# ProPrj__-END_2025-01-18.net
KiCad netlist of a schematic drawn in EasyEDA Pro
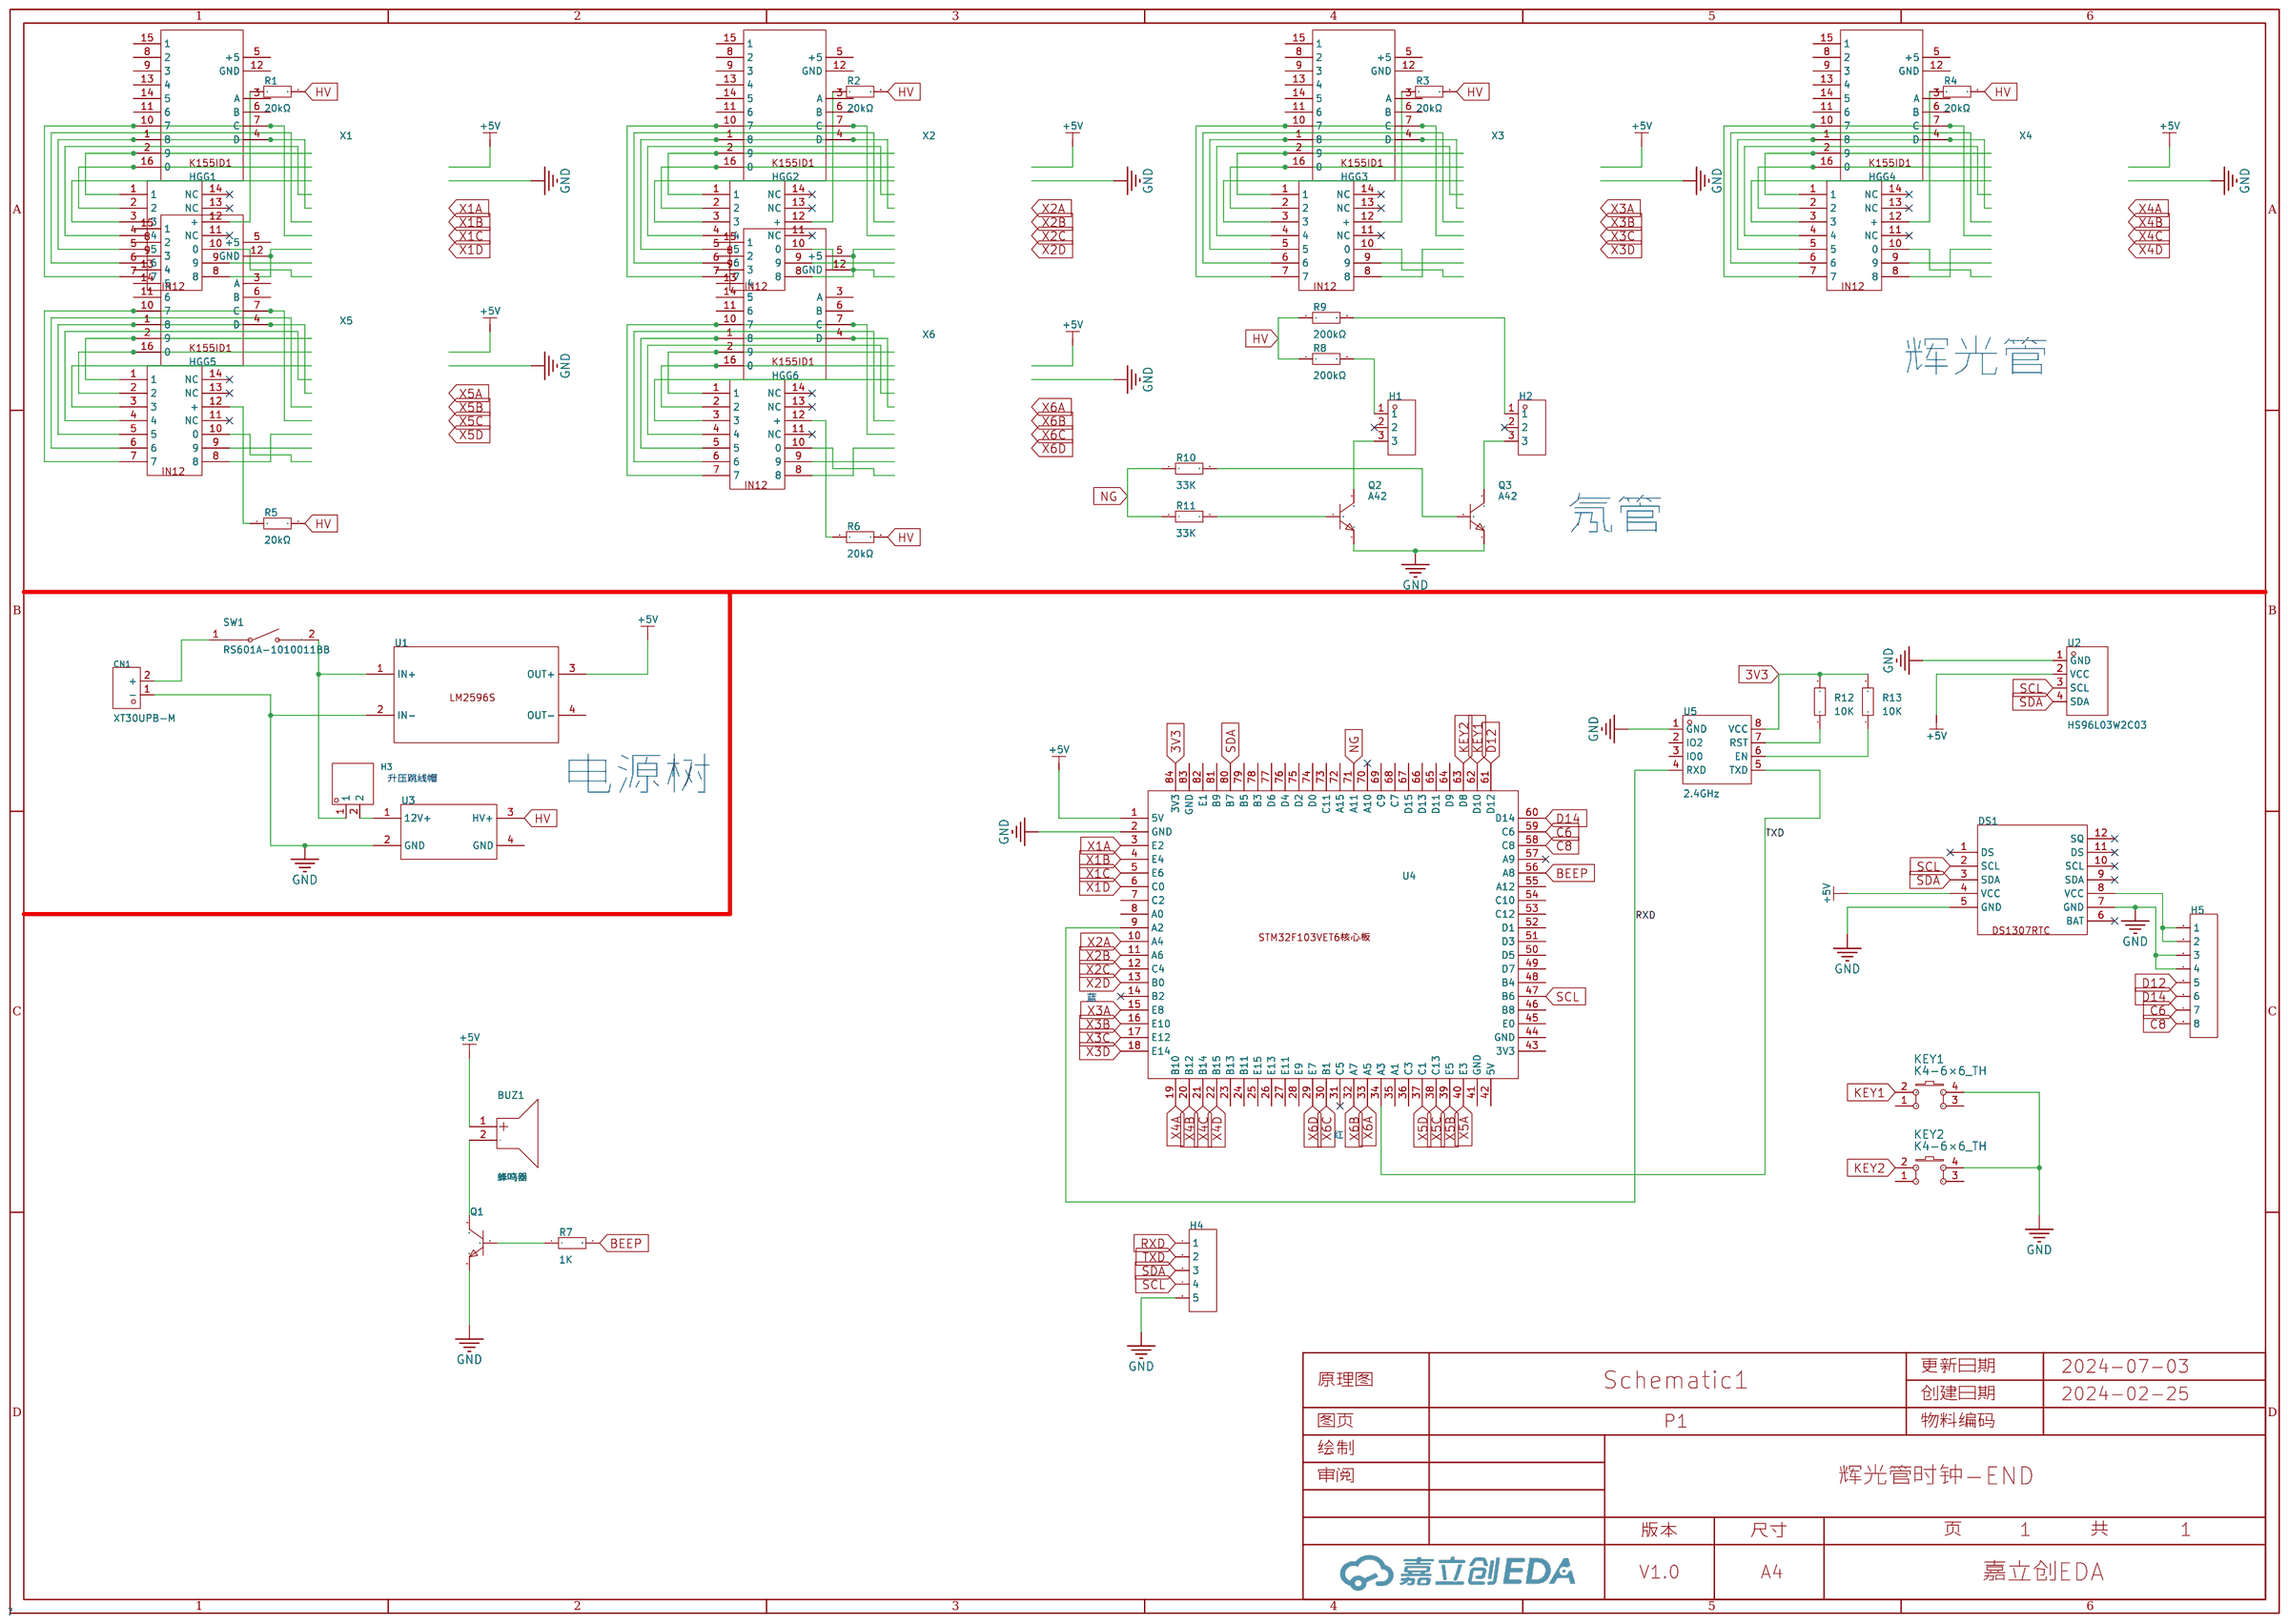
[diagram p0: schematic sheet]

(export (version "E")
  (design (tool "Eeschema 10.0.6"))
  (components
    (comp (ref "BUZ1")
      (value "蜂鸣器")
      (footprint "easyedapro:BUZ-TH_BD9.0-P5.00-D0.6-FD")
      (libsource (lib "easyedapro") (part "蜂鸣器"))
    )
    (comp (ref "CN1")
      (value "XT30UPB-M")
      (footprint "easyedapro:CONN-TH_XT30UPB-M")
      (description "类别:-;类型1:-;")
      (fields (field (name "Manufacturer") "AMASS(艾迈斯)"))
      (libsource (lib "easyedapro") (part "XT30UPB-M"))
    )
    (comp (ref "DS1")
      (value "~")
      (footprint "easyedapro:Tiny RTC")
      (description "DS1307模块")
      (libsource (lib "easyedapro") (part "DS1307模块IIC"))
    )
    (comp (ref "H1")
      (value "~")
      (footprint "easyedapro:HDR-TH_3P-P2.54-V-F")
      (libsource (lib "easyedapro") (part "PM254V-11-03-H85"))
    )
    (comp (ref "H2")
      (value "~")
      (footprint "easyedapro:HDR-TH_3P-P2.54-V-F")
      (libsource (lib "easyedapro") (part "PM254V-11-03-H85"))
    )
    (comp (ref "H3")
      (value "~")
      (footprint "easyedapro:HDR-TH_2P-P2.54-V-M-1")
      (libsource (lib "easyedapro") (part "210S-1*2P L=11.6MMGold-plated black"))
    )
    (comp (ref "H4")
      (value "~")
      (footprint "easyedapro:HDR-TH_5P-P2.54-V-F")
      (libsource (lib "easyedapro") (part "Header-Female-2.54_1x5"))
    )
    (comp (ref "H5")
      (value "~")
      (footprint "easyedapro:HDR-TH_8P-P2.54-V-F-1")
      (libsource (lib "easyedapro") (part "Header-Female-2.54_1x8"))
    )
    (comp (ref "HGG1")
      (value "~")
      (footprint "easyedapro:IN12-6")
      (libsource (lib "easyedapro") (part "辉光管IN12"))
    )
    (comp (ref "HGG2")
      (value "~")
      (footprint "easyedapro:IN12-6")
      (libsource (lib "easyedapro") (part "辉光管IN12"))
    )
    (comp (ref "HGG3")
      (value "~")
      (footprint "easyedapro:IN12-6")
      (libsource (lib "easyedapro") (part "辉光管IN12"))
    )
    (comp (ref "HGG4")
      (value "~")
      (footprint "easyedapro:IN12-6")
      (libsource (lib "easyedapro") (part "辉光管IN12"))
    )
    (comp (ref "HGG5")
      (value "~")
      (footprint "easyedapro:IN12-6")
      (libsource (lib "easyedapro") (part "辉光管IN12"))
    )
    (comp (ref "HGG6")
      (value "~")
      (footprint "easyedapro:IN12-6")
      (libsource (lib "easyedapro") (part "辉光管IN12"))
    )
    (comp (ref "KEY1")
      (value "K4-6×6_TH")
      (footprint "easyedapro:KEY-TH_4P-L6.0-W6.0-P4.50-LS6.5")
      (fields (field (name "Manufacturer Part") "K2-1102DP-E4SW-04") (field (name "Manufacturer") "韩国韩荣"))
      (libsource (lib "easyedapro") (part "K4-6×6_TH"))
    )
    (comp (ref "KEY2")
      (value "K4-6×6_TH")
      (footprint "easyedapro:KEY-TH_4P-L6.0-W6.0-P4.50-LS6.5")
      (fields (field (name "Manufacturer Part") "K2-1102DP-E4SW-04") (field (name "Manufacturer") "韩国韩荣"))
      (libsource (lib "easyedapro") (part "K4-6×6_TH"))
    )
    (comp (ref "Q1")
      (value "~")
      (footprint "easyedapro:S8050_SOT-23")
      (libsource (lib "easyedapro") (part "NPN"))
    )
    (comp (ref "Q2")
      (value "A42")
      (footprint "easyedapro:TO-92-3_L5.1-W4.1-P1.27-L")
      (description "晶体管类型:NPN;集电极电流(Ic):200mA;集射极击穿电压(Vceo):305V;功率(Pd):625mW;直流电流增益(hFE@Ic,Vce):100@10mA,10V;")
      (fields (field (name "Manufacturer") "CJ(江苏长电/长晶)"))
      (libsource (lib "easyedapro") (part "A42"))
    )
    (comp (ref "Q3")
      (value "A42")
      (footprint "easyedapro:TO-92-3_L5.1-W4.1-P1.27-L")
      (description "晶体管类型:NPN;集电极电流(Ic):200mA;集射极击穿电压(Vceo):305V;功率(Pd):625mW;直流电流增益(hFE@Ic,Vce):100@10mA,10V;")
      (fields (field (name "Manufacturer") "CJ(江苏长电/长晶)"))
      (libsource (lib "easyedapro") (part "A42"))
    )
    (comp (ref "R1")
      (value "20kΩ")
      (footprint "easyedapro:RES-TH_BD2.2-L6.5-P10.50-D0.6")
      (description "电阻类型:金属膜电阻;阻值:20kΩ;精度:±1%;功率:250mW;温度系数:±50ppm/°C;")
      (fields
        (field (name "Manufacturer Part") "MFR0W4F2002A50")
        (field (name "Manufacturer") "UNI-ROYAL(厚声)")
      )
      (libsource (lib "easyedapro") (part "MFR0W4F2002A50"))
    )
    (comp (ref "R2")
      (value "20kΩ")
      (footprint "easyedapro:RES-TH_BD2.2-L6.5-P10.50-D0.6")
      (description "电阻类型:金属膜电阻;阻值:20kΩ;精度:±1%;功率:250mW;温度系数:±50ppm/°C;")
      (fields
        (field (name "Manufacturer Part") "MFR0W4F2002A50")
        (field (name "Manufacturer") "UNI-ROYAL(厚声)")
      )
      (libsource (lib "easyedapro") (part "MFR0W4F2002A50"))
    )
    (comp (ref "R3")
      (value "20kΩ")
      (footprint "easyedapro:RES-TH_BD2.2-L6.5-P10.50-D0.6")
      (description "电阻类型:金属膜电阻;阻值:20kΩ;精度:±1%;功率:250mW;温度系数:±50ppm/°C;")
      (fields
        (field (name "Manufacturer Part") "MFR0W4F2002A50")
        (field (name "Manufacturer") "UNI-ROYAL(厚声)")
      )
      (libsource (lib "easyedapro") (part "MFR0W4F2002A50"))
    )
    (comp (ref "R4")
      (value "20kΩ")
      (footprint "easyedapro:RES-TH_BD2.2-L6.5-P10.50-D0.6")
      (description "电阻类型:金属膜电阻;阻值:20kΩ;精度:±1%;功率:250mW;温度系数:±50ppm/°C;")
      (fields
        (field (name "Manufacturer Part") "MFR0W4F2002A50")
        (field (name "Manufacturer") "UNI-ROYAL(厚声)")
      )
      (libsource (lib "easyedapro") (part "MFR0W4F2002A50"))
    )
    (comp (ref "R5")
      (value "20kΩ")
      (footprint "easyedapro:RES-TH_BD2.2-L6.5-P10.50-D0.6")
      (description "电阻类型:金属膜电阻;阻值:20kΩ;精度:±1%;功率:250mW;温度系数:±50ppm/°C;")
      (fields
        (field (name "Manufacturer Part") "MFR0W4F2002A50")
        (field (name "Manufacturer") "UNI-ROYAL(厚声)")
      )
      (libsource (lib "easyedapro") (part "MFR0W4F2002A50"))
    )
    (comp (ref "R6")
      (value "20kΩ")
      (footprint "easyedapro:RES-TH_BD2.2-L6.5-P10.50-D0.6")
      (description "电阻类型:金属膜电阻;阻值:20kΩ;精度:±1%;功率:250mW;温度系数:±50ppm/°C;")
      (fields
        (field (name "Manufacturer Part") "MFR0W4F2002A50")
        (field (name "Manufacturer") "UNI-ROYAL(厚声)")
      )
      (libsource (lib "easyedapro") (part "MFR0W4F2002A50"))
    )
    (comp (ref "R7") (value "1K") (footprint "easyedapro:R0805") (libsource (lib "easyedapro") (part "电阻")))
    (comp (ref "R8")
      (value "200kΩ")
      (footprint "easyedapro:R0805")
      (libsource (lib "easyedapro") (part "电阻"))
    )
    (comp (ref "R9")
      (value "200kΩ")
      (footprint "easyedapro:R0805")
      (libsource (lib "easyedapro") (part "电阻"))
    )
    (comp (ref "R10") (value "33K") (footprint "easyedapro:R0805") (libsource (lib "easyedapro") (part "电阻")))
    (comp (ref "R11") (value "33K") (footprint "easyedapro:R0805") (libsource (lib "easyedapro") (part "电阻")))
    (comp (ref "R12") (value "10K") (footprint "easyedapro:R0805") (libsource (lib "easyedapro") (part "电阻")))
    (comp (ref "R13") (value "10K") (footprint "easyedapro:R0805") (libsource (lib "easyedapro") (part "电阻")))
    (comp (ref "SW1")
      (value "RS601A-1010011BB")
      (footprint "easyedapro:SW-TH_RS601A-1010011BB")
      (fields (field (name "Manufacturer") "LECI(乐磁)"))
      (libsource (lib "easyedapro") (part "RS601A-1010011BB"))
    )
    (comp (ref "U1")
      (value "~")
      (footprint "easyedapro:LM2596S降压模块")
      (libsource (lib "easyedapro") (part "LM2569S降压模块"))
    )
    (comp (ref "U2")
      (value "HS96L03W2C03")
      (footprint "easyedapro:OLED-TH_L27.8-W27.2-P2.54_C9900033791")
      (description "主控芯片:SSD1315;接口类型:I2C;尺寸(inch):0.96;像素分辨率:128x64;")
      (fields (field (name "Manufacturer") "HS(汉昇)"))
      (libsource (lib "easyedapro") (part "HS96L03W2C03"))
    )
    (comp (ref "U3")
      (value "~")
      (footprint "easyedapro:升压模块2")
      (description "给辉光管升压的模块")
      (libsource (lib "easyedapro") (part "辉光管升压模块"))
    )
    (comp (ref "U4")
      (value "~")
      (footprint "easyedapro:魔女STM32F103VET6核心板")
      (libsource (lib "easyedapro") (part "魔女STM32F103VET6核心板"))
    )
    (comp (ref "U5")
      (value "2.4GHz")
      (footprint "easyedapro:WIFIM-TH_8P-L24.7-W14.4-P2.54")
      (description "核心处理器:ESP8266芯片;频率:2.4GHz;天线形式:板载PCB天线;发射功率:16dBm;接收灵敏度:-90dBm;")
      (fields (field (name "Manufacturer Part") "ESP-01S") (field (name "Manufacturer") "Ai-Thinker(安信可)"))
      (libsource (lib "easyedapro") (part "ESP-01S_C503582"))
    )
    (comp (ref "X1")
      (value "~")
      (footprint "easyedapro:K155ID1")
      (libsource (lib "easyedapro") (part "K155ID1"))
    )
    (comp (ref "X2")
      (value "~")
      (footprint "easyedapro:K155ID1")
      (libsource (lib "easyedapro") (part "K155ID1"))
    )
    (comp (ref "X3")
      (value "~")
      (footprint "easyedapro:K155ID1")
      (libsource (lib "easyedapro") (part "K155ID1"))
    )
    (comp (ref "X4")
      (value "~")
      (footprint "easyedapro:K155ID1")
      (libsource (lib "easyedapro") (part "K155ID1"))
    )
    (comp (ref "X5")
      (value "~")
      (footprint "easyedapro:K155ID1")
      (libsource (lib "easyedapro") (part "K155ID1"))
    )
    (comp (ref "X6")
      (value "~")
      (footprint "easyedapro:K155ID1")
      (libsource (lib "easyedapro") (part "K155ID1"))
    )
  )
  (nets
    (net (code "1") (name "+5V") (class "Default")
      (node (ref "BUZ1") (pin "1") (pinfunction "+_1") (pintype "unspecified"))
      (node (ref "DS1") (pin "4") (pinfunction "VCC_4") (pintype "input"))
      (node (ref "U1") (pin "3") (pinfunction "OUT+_3") (pintype "input"))
      (node (ref "U2") (pin "2") (pinfunction "VCC_2") (pintype "unspecified"))
      (node (ref "U4") (pin "1") (pinfunction "5V_1") (pintype "input"))
    )
    (net (code "2") (name "3V3") (class "Default")
      (node (ref "R12") (pin "2") (pinfunction "2_2") (pintype "input"))
      (node (ref "R13") (pin "2") (pinfunction "2_2") (pintype "input"))
      (node (ref "U4") (pin "84") (pinfunction "3V3_84") (pintype "input"))
      (node (ref "U5") (pin "8") (pinfunction "VCC_8") (pintype "input"))
    )
    (net (code "3") (name "BEEP") (class "Default")
      (node (ref "R7") (pin "2") (pinfunction "2_2") (pintype "input"))
      (node (ref "U4") (pin "56") (pinfunction "A8_56") (pintype "input"))
    )
    (net (code "4") (name "C6") (class "Default")
      (node (ref "H5") (pin "7") (pinfunction "7_7") (pintype "input"))
      (node (ref "U4") (pin "59") (pinfunction "C6_59") (pintype "input"))
    )
    (net (code "5") (name "C8") (class "Default")
      (node (ref "H5") (pin "8") (pinfunction "8_8") (pintype "input"))
      (node (ref "U4") (pin "58") (pinfunction "C8_58") (pintype "input"))
    )
    (net (code "6") (name "D12") (class "Default")
      (node (ref "H5") (pin "5") (pinfunction "5_5") (pintype "input"))
      (node (ref "U4") (pin "61") (pinfunction "D12_61") (pintype "input"))
    )
    (net (code "7") (name "D14") (class "Default")
      (node (ref "H5") (pin "6") (pinfunction "6_6") (pintype "input"))
      (node (ref "U4") (pin "60") (pinfunction "D14_60") (pintype "input"))
    )
    (net (code "8") (name "GND") (class "Default")
      (node (ref "CN1") (pin "1") (pinfunction "-_1") (pintype "input"))
      (node (ref "DS1") (pin "5") (pinfunction "GND_5") (pintype "input"))
      (node (ref "DS1") (pin "7") (pinfunction "GND_7") (pintype "input"))
      (node (ref "H4") (pin "5") (pinfunction "5_5") (pintype "input"))
      (node (ref "H5") (pin "3") (pinfunction "3_3") (pintype "input"))
      (node (ref "H5") (pin "4") (pinfunction "4_4") (pintype "input"))
      (node (ref "KEY1") (pin "4") (pinfunction "4_4") (pintype "input"))
      (node (ref "KEY2") (pin "4") (pinfunction "4_4") (pintype "input"))
      (node (ref "Q1") (pin "2") (pinfunction "2_2") (pintype "unspecified"))
      (node (ref "Q2") (pin "1") (pinfunction "E_1") (pintype "unspecified"))
      (node (ref "Q3") (pin "1") (pinfunction "E_1") (pintype "unspecified"))
      (node (ref "U1") (pin "2") (pinfunction "IN-_2") (pintype "input"))
      (node (ref "U2") (pin "1") (pinfunction "GND_1") (pintype "unspecified"))
      (node (ref "U3") (pin "2") (pinfunction "GND_2") (pintype "input"))
      (node (ref "U4") (pin "2") (pinfunction "GND_2") (pintype "input"))
      (node (ref "U5") (pin "1") (pinfunction "GND_1") (pintype "input"))
    )
    (net (code "9") (name "HV") (class "Default")
      (node (ref "R1") (pin "2") (pinfunction "2_2") (pintype "input"))
      (node (ref "R2") (pin "2") (pinfunction "2_2") (pintype "input"))
      (node (ref "R3") (pin "2") (pinfunction "2_2") (pintype "input"))
      (node (ref "R4") (pin "2") (pinfunction "2_2") (pintype "input"))
      (node (ref "R5") (pin "2") (pinfunction "2_2") (pintype "input"))
      (node (ref "R6") (pin "2") (pinfunction "2_2") (pintype "input"))
      (node (ref "R8") (pin "1") (pinfunction "1_1") (pintype "input"))
      (node (ref "R9") (pin "1") (pinfunction "1_1") (pintype "input"))
      (node (ref "U3") (pin "3") (pinfunction "HV+_3") (pintype "input"))
    )
    (net (code "10") (name "KEY1") (class "Default")
      (node (ref "KEY1") (pin "2") (pinfunction "2_2") (pintype "input"))
      (node (ref "U4") (pin "62") (pinfunction "D10_62") (pintype "input"))
    )
    (net (code "11") (name "KEY2") (class "Default")
      (node (ref "KEY2") (pin "2") (pinfunction "2_2") (pintype "input"))
      (node (ref "U4") (pin "63") (pinfunction "D8_63") (pintype "input"))
    )
    (net (code "12") (name "NG") (class "Default")
      (node (ref "R10") (pin "1") (pinfunction "1_1") (pintype "input"))
      (node (ref "R11") (pin "1") (pinfunction "1_1") (pintype "input"))
      (node (ref "U4") (pin "71") (pinfunction "A11_71") (pintype "input"))
    )
    (net (code "13") (name "Net-(BUZ1--)") (class "Default")
      (node (ref "BUZ1") (pin "2") (pinfunction "-_2") (pintype "unspecified"))
      (node (ref "Q1") (pin "3") (pinfunction "3_3") (pintype "unspecified"))
    )
    (net (code "14") (name "Net-(CN1-+)") (class "Default")
      (node (ref "CN1") (pin "2") (pinfunction "+_2") (pintype "input"))
      (node (ref "SW1") (pin "1") (pinfunction "1_1") (pintype "input"))
    )
    (net (code "15") (name "Net-(DS1-VCC-Pad8)") (class "Default")
      (node (ref "DS1") (pin "8") (pinfunction "VCC_8") (pintype "input"))
      (node (ref "H5") (pin "1") (pinfunction "1_1") (pintype "input"))
      (node (ref "H5") (pin "2") (pinfunction "2_2") (pintype "input"))
    )
    (net (code "16") (name "Net-(H1-Pad1)") (class "Default")
      (node (ref "H1") (pin "1") (pinfunction "1_1") (pintype "unspecified"))
      (node (ref "R8") (pin "2") (pinfunction "2_2") (pintype "input"))
    )
    (net (code "17") (name "Net-(H2-Pad1)") (class "Default")
      (node (ref "H2") (pin "1") (pinfunction "1_1") (pintype "unspecified"))
      (node (ref "R9") (pin "2") (pinfunction "2_2") (pintype "input"))
    )
    (net (code "18") (name "Net-(HGG1-+)") (class "Default")
      (node (ref "HGG1") (pin "12") (pinfunction "+_12") (pintype "input"))
      (node (ref "R1") (pin "1") (pinfunction "1_1") (pintype "input"))
    )
    (net (code "19") (name "Net-(HGG2-+)") (class "Default")
      (node (ref "HGG2") (pin "12") (pinfunction "+_12") (pintype "input"))
      (node (ref "R2") (pin "1") (pinfunction "1_1") (pintype "input"))
    )
    (net (code "20") (name "Net-(HGG2-0)") (class "Default")
      (node (ref "HGG2") (pin "10") (pinfunction "0_10") (pintype "input"))
      (node (ref "HGG2") (pin "8") (pinfunction "8_8") (pintype "input"))
      (node (ref "X6") (pin "12") (pinfunction "GND_12") (pintype "input"))
      (node (ref "X6") (pin "5") (pinfunction "+5_5") (pintype "input"))
    )
    (net (code "21") (name "Net-(HGG3-+)") (class "Default")
      (node (ref "HGG3") (pin "12") (pinfunction "+_12") (pintype "input"))
      (node (ref "R3") (pin "1") (pinfunction "1_1") (pintype "input"))
    )
    (net (code "22") (name "Net-(HGG4-+)") (class "Default")
      (node (ref "HGG4") (pin "12") (pinfunction "+_12") (pintype "input"))
      (node (ref "R4") (pin "1") (pinfunction "1_1") (pintype "input"))
    )
    (net (code "23") (name "Net-(HGG5-+)") (class "Default")
      (node (ref "HGG5") (pin "12") (pinfunction "+_12") (pintype "input"))
      (node (ref "R5") (pin "1") (pinfunction "1_1") (pintype "input"))
    )
    (net (code "24") (name "Net-(HGG6-+)") (class "Default")
      (node (ref "HGG6") (pin "12") (pinfunction "+_12") (pintype "input"))
      (node (ref "R6") (pin "1") (pinfunction "1_1") (pintype "input"))
    )
    (net (code "25") (name "Net-(Q1-Pad1)") (class "Default")
      (node (ref "Q1") (pin "1") (pinfunction "1_1") (pintype "unspecified"))
      (node (ref "R7") (pin "1") (pinfunction "1_1") (pintype "input"))
    )
    (net (code "26") (name "Net-(Q2-B)") (class "Default")
      (node (ref "Q2") (pin "2") (pinfunction "B_2") (pintype "unspecified"))
      (node (ref "R11") (pin "2") (pinfunction "2_2") (pintype "input"))
    )
    (net (code "27") (name "Net-(Q2-C)") (class "Default")
      (node (ref "H1") (pin "3") (pinfunction "3_3") (pintype "unspecified"))
      (node (ref "Q2") (pin "3") (pinfunction "C_3") (pintype "unspecified"))
    )
    (net (code "28") (name "Net-(Q3-B)") (class "Default")
      (node (ref "Q3") (pin "2") (pinfunction "B_2") (pintype "unspecified"))
      (node (ref "R10") (pin "2") (pinfunction "2_2") (pintype "input"))
    )
    (net (code "29") (name "Net-(Q3-C)") (class "Default")
      (node (ref "H2") (pin "3") (pinfunction "3_3") (pintype "unspecified"))
      (node (ref "Q3") (pin "3") (pinfunction "C_3") (pintype "unspecified"))
    )
    (net (code "30") (name "Net-(U1-IN+)") (class "Default")
      (node (ref "H3") (pin "1") (pinfunction "1_1") (pintype "input"))
      (node (ref "SW1") (pin "2") (pinfunction "2_2") (pintype "input"))
      (node (ref "U1") (pin "1") (pinfunction "IN+_1") (pintype "input"))
    )
    (net (code "31") (name "Net-(U3-12V+)") (class "Default")
      (node (ref "H3") (pin "2") (pinfunction "2_2") (pintype "input"))
      (node (ref "U3") (pin "1") (pinfunction "12V+_1") (pintype "input"))
    )
    (net (code "32") (name "Net-(U5-EN)") (class "Default")
      (node (ref "R13") (pin "1") (pinfunction "1_1") (pintype "input"))
      (node (ref "U5") (pin "6") (pinfunction "EN_6") (pintype "input"))
    )
    (net (code "33") (name "Net-(U5-RST)") (class "Default")
      (node (ref "R12") (pin "1") (pinfunction "1_1") (pintype "input"))
      (node (ref "U5") (pin "7") (pinfunction "RST_7") (pintype "input"))
    )
    (net (code "34") (name "Net-(X1-0)") (class "Default")
      (node (ref "HGG1") (pin "2") (pinfunction "2_2") (pintype "input"))
      (node (ref "X1") (pin "16") (pinfunction "0_16") (pintype "input"))
    )
    (net (code "35") (name "Net-(X1-7)") (class "Default")
      (node (ref "HGG1") (pin "7") (pinfunction "7_7") (pintype "input"))
      (node (ref "X1") (pin "10") (pinfunction "7_10") (pintype "input"))
      (node (ref "X1") (pin "7") (pinfunction "C_7") (pintype "input"))
    )
    (net (code "36") (name "Net-(X1-8)") (class "Default")
      (node (ref "HGG1") (pin "5") (pinfunction "5_5") (pintype "input"))
      (node (ref "X1") (pin "1") (pinfunction "8_1") (pintype "input"))
      (node (ref "X1") (pin "4") (pinfunction "D_4") (pintype "input"))
    )
    (net (code "37") (name "Net-(X1-9)") (class "Default")
      (node (ref "HGG1") (pin "1") (pinfunction "1_1") (pintype "input"))
      (node (ref "X1") (pin "2") (pinfunction "9_2") (pintype "input"))
    )
    (net (code "38") (name "Net-(X2-0)") (class "Default")
      (node (ref "HGG2") (pin "2") (pinfunction "2_2") (pintype "input"))
      (node (ref "X2") (pin "16") (pinfunction "0_16") (pintype "input"))
    )
    (net (code "39") (name "Net-(X2-7)") (class "Default")
      (node (ref "HGG2") (pin "7") (pinfunction "7_7") (pintype "input"))
      (node (ref "X2") (pin "10") (pinfunction "7_10") (pintype "input"))
      (node (ref "X2") (pin "7") (pinfunction "C_7") (pintype "input"))
    )
    (net (code "40") (name "Net-(X2-8)") (class "Default")
      (node (ref "HGG2") (pin "5") (pinfunction "5_5") (pintype "input"))
      (node (ref "X2") (pin "1") (pinfunction "8_1") (pintype "input"))
      (node (ref "X2") (pin "4") (pinfunction "D_4") (pintype "input"))
    )
    (net (code "41") (name "Net-(X2-9)") (class "Default")
      (node (ref "HGG2") (pin "1") (pinfunction "1_1") (pintype "input"))
      (node (ref "X2") (pin "2") (pinfunction "9_2") (pintype "input"))
    )
    (net (code "42") (name "Net-(X3-0)") (class "Default")
      (node (ref "HGG3") (pin "2") (pinfunction "2_2") (pintype "input"))
      (node (ref "X3") (pin "16") (pinfunction "0_16") (pintype "input"))
    )
    (net (code "43") (name "Net-(X3-7)") (class "Default")
      (node (ref "HGG3") (pin "7") (pinfunction "7_7") (pintype "input"))
      (node (ref "X3") (pin "10") (pinfunction "7_10") (pintype "input"))
      (node (ref "X3") (pin "7") (pinfunction "C_7") (pintype "input"))
    )
    (net (code "44") (name "Net-(X3-8)") (class "Default")
      (node (ref "HGG3") (pin "5") (pinfunction "5_5") (pintype "input"))
      (node (ref "X3") (pin "1") (pinfunction "8_1") (pintype "input"))
      (node (ref "X3") (pin "4") (pinfunction "D_4") (pintype "input"))
    )
    (net (code "45") (name "Net-(X3-9)") (class "Default")
      (node (ref "HGG3") (pin "1") (pinfunction "1_1") (pintype "input"))
      (node (ref "X3") (pin "2") (pinfunction "9_2") (pintype "input"))
    )
    (net (code "46") (name "Net-(X4-0)") (class "Default")
      (node (ref "HGG4") (pin "2") (pinfunction "2_2") (pintype "input"))
      (node (ref "X4") (pin "16") (pinfunction "0_16") (pintype "input"))
    )
    (net (code "47") (name "Net-(X4-7)") (class "Default")
      (node (ref "HGG4") (pin "7") (pinfunction "7_7") (pintype "input"))
      (node (ref "X4") (pin "10") (pinfunction "7_10") (pintype "input"))
      (node (ref "X4") (pin "7") (pinfunction "C_7") (pintype "input"))
    )
    (net (code "48") (name "Net-(X4-8)") (class "Default")
      (node (ref "HGG4") (pin "5") (pinfunction "5_5") (pintype "input"))
      (node (ref "X4") (pin "1") (pinfunction "8_1") (pintype "input"))
      (node (ref "X4") (pin "4") (pinfunction "D_4") (pintype "input"))
    )
    (net (code "49") (name "Net-(X4-9)") (class "Default")
      (node (ref "HGG4") (pin "1") (pinfunction "1_1") (pintype "input"))
      (node (ref "X4") (pin "2") (pinfunction "9_2") (pintype "input"))
    )
    (net (code "50") (name "Net-(X5-0)") (class "Default")
      (node (ref "HGG5") (pin "2") (pinfunction "2_2") (pintype "input"))
      (node (ref "X5") (pin "16") (pinfunction "0_16") (pintype "input"))
    )
    (net (code "51") (name "Net-(X5-7)") (class "Default")
      (node (ref "HGG5") (pin "7") (pinfunction "7_7") (pintype "input"))
      (node (ref "X5") (pin "10") (pinfunction "7_10") (pintype "input"))
      (node (ref "X5") (pin "7") (pinfunction "C_7") (pintype "input"))
    )
    (net (code "52") (name "Net-(X5-8)") (class "Default")
      (node (ref "HGG5") (pin "5") (pinfunction "5_5") (pintype "input"))
      (node (ref "X5") (pin "1") (pinfunction "8_1") (pintype "input"))
      (node (ref "X5") (pin "4") (pinfunction "D_4") (pintype "input"))
    )
    (net (code "53") (name "Net-(X5-9)") (class "Default")
      (node (ref "HGG5") (pin "1") (pinfunction "1_1") (pintype "input"))
      (node (ref "X5") (pin "2") (pinfunction "9_2") (pintype "input"))
    )
    (net (code "54") (name "Net-(X5-GND)") (class "Default")
      (node (ref "HGG1") (pin "8") (pinfunction "8_8") (pintype "input"))
      (node (ref "X5") (pin "12") (pinfunction "GND_12") (pintype "input"))
    )
    (net (code "55") (name "Net-(X6-0)") (class "Default")
      (node (ref "HGG6") (pin "2") (pinfunction "2_2") (pintype "input"))
      (node (ref "X6") (pin "16") (pinfunction "0_16") (pintype "input"))
    )
    (net (code "56") (name "Net-(X6-7)") (class "Default")
      (node (ref "HGG6") (pin "7") (pinfunction "7_7") (pintype "input"))
      (node (ref "X6") (pin "10") (pinfunction "7_10") (pintype "input"))
      (node (ref "X6") (pin "7") (pinfunction "C_7") (pintype "input"))
    )
    (net (code "57") (name "Net-(X6-8)") (class "Default")
      (node (ref "HGG6") (pin "5") (pinfunction "5_5") (pintype "input"))
      (node (ref "X6") (pin "1") (pinfunction "8_1") (pintype "input"))
      (node (ref "X6") (pin "4") (pinfunction "D_4") (pintype "input"))
    )
    (net (code "58") (name "Net-(X6-9)") (class "Default")
      (node (ref "HGG6") (pin "1") (pinfunction "1_1") (pintype "input"))
      (node (ref "X6") (pin "2") (pinfunction "9_2") (pintype "input"))
    )
    (net (code "59") (name "RXD") (class "Default")
      (node (ref "H4") (pin "1") (pinfunction "1_1") (pintype "input"))
      (node (ref "U4") (pin "9") (pinfunction "A2_9") (pintype "input"))
      (node (ref "U5") (pin "4") (pinfunction "RXD_4") (pintype "input"))
    )
    (net (code "60") (name "SCL") (class "Default")
      (node (ref "DS1") (pin "2") (pinfunction "SCL_2") (pintype "input"))
      (node (ref "H4") (pin "4") (pinfunction "4_4") (pintype "input"))
      (node (ref "U2") (pin "3") (pinfunction "SCL_3") (pintype "unspecified"))
      (node (ref "U4") (pin "47") (pinfunction "B6_47") (pintype "input"))
    )
    (net (code "61") (name "SDA") (class "Default")
      (node (ref "DS1") (pin "3") (pinfunction "SDA_3") (pintype "input"))
      (node (ref "H4") (pin "3") (pinfunction "3_3") (pintype "input"))
      (node (ref "U2") (pin "4") (pinfunction "SDA_4") (pintype "unspecified"))
      (node (ref "U4") (pin "80") (pinfunction "B7_80") (pintype "input"))
    )
    (net (code "62") (name "TXD") (class "Default")
      (node (ref "H4") (pin "2") (pinfunction "2_2") (pintype "input"))
      (node (ref "U4") (pin "34") (pinfunction "A3_34") (pintype "input"))
      (node (ref "U5") (pin "5") (pinfunction "TXD_5") (pintype "input"))
    )
    (net (code "63") (name "X1A") (class "Default")
      (node (ref "U4") (pin "3") (pinfunction "E2_3") (pintype "input"))
    )
    (net (code "64") (name "X1B") (class "Default")
      (node (ref "U4") (pin "4") (pinfunction "E4_4") (pintype "input"))
    )
    (net (code "65") (name "X1C") (class "Default")
      (node (ref "U4") (pin "5") (pinfunction "E6_5") (pintype "input"))
    )
    (net (code "66") (name "X1D") (class "Default")
      (node (ref "U4") (pin "6") (pinfunction "C0_6") (pintype "input"))
    )
    (net (code "67") (name "X2A") (class "Default")
      (node (ref "U4") (pin "10") (pinfunction "A4_10") (pintype "input"))
    )
    (net (code "68") (name "X2B") (class "Default")
      (node (ref "U4") (pin "11") (pinfunction "A6_11") (pintype "input"))
    )
    (net (code "69") (name "X2C") (class "Default")
      (node (ref "U4") (pin "12") (pinfunction "C4_12") (pintype "input"))
    )
    (net (code "70") (name "X2D") (class "Default")
      (node (ref "U4") (pin "13") (pinfunction "B0_13") (pintype "input"))
    )
    (net (code "71") (name "X3A") (class "Default")
      (node (ref "U4") (pin "15") (pinfunction "E8_15") (pintype "input"))
    )
    (net (code "72") (name "X3B") (class "Default")
      (node (ref "U4") (pin "16") (pinfunction "E10_16") (pintype "input"))
    )
    (net (code "73") (name "X3C") (class "Default")
      (node (ref "U4") (pin "17") (pinfunction "E12_17") (pintype "input"))
    )
    (net (code "74") (name "X3D") (class "Default")
      (node (ref "U4") (pin "18") (pinfunction "E14_18") (pintype "input"))
    )
    (net (code "75") (name "X4A") (class "Default")
      (node (ref "U4") (pin "19") (pinfunction "B10_19") (pintype "input"))
    )
    (net (code "76") (name "X4B") (class "Default")
      (node (ref "U4") (pin "20") (pinfunction "B12_20") (pintype "input"))
    )
    (net (code "77") (name "X4C") (class "Default")
      (node (ref "U4") (pin "21") (pinfunction "B14_21") (pintype "input"))
    )
    (net (code "78") (name "X4D") (class "Default")
      (node (ref "U4") (pin "22") (pinfunction "B15_22") (pintype "input"))
    )
    (net (code "79") (name "X5A") (class "Default")
      (node (ref "U4") (pin "40") (pinfunction "E3_40") (pintype "input"))
    )
    (net (code "80") (name "X5B") (class "Default")
      (node (ref "U4") (pin "39") (pinfunction "E5_39") (pintype "input"))
    )
    (net (code "81") (name "X5C") (class "Default")
      (node (ref "U4") (pin "38") (pinfunction "C13_38") (pintype "input"))
    )
    (net (code "82") (name "X5D") (class "Default")
      (node (ref "U4") (pin "37") (pinfunction "C1_37") (pintype "input"))
    )
    (net (code "83") (name "X6A") (class "Default")
      (node (ref "U4") (pin "33") (pinfunction "A5_33") (pintype "input"))
    )
    (net (code "84") (name "X6B") (class "Default")
      (node (ref "U4") (pin "32") (pinfunction "A7_32") (pintype "input"))
    )
    (net (code "85") (name "X6C") (class "Default")
      (node (ref "U4") (pin "30") (pinfunction "B1_30") (pintype "input"))
    )
    (net (code "86") (name "X6D") (class "Default")
      (node (ref "U4") (pin "29") (pinfunction "E7_29") (pintype "input"))
    )
    (net (code "87") (name "unconnected-(DS1-BAT-Pad6)") (class "Default")
      (node (ref "DS1") (pin "6") (pinfunction "BAT_6") (pintype "input+no_connect"))
    )
    (net (code "88") (name "unconnected-(DS1-DS-Pad1)") (class "Default")
      (node (ref "DS1") (pin "1") (pinfunction "DS_1") (pintype "input+no_connect"))
    )
    (net (code "89") (name "unconnected-(DS1-DS-Pad11)") (class "Default")
      (node (ref "DS1") (pin "11") (pinfunction "DS_11") (pintype "input+no_connect"))
    )
    (net (code "90") (name "unconnected-(DS1-SCL-Pad10)") (class "Default")
      (node (ref "DS1") (pin "10") (pinfunction "SCL_10") (pintype "input+no_connect"))
    )
    (net (code "91") (name "unconnected-(DS1-SDA-Pad9)") (class "Default")
      (node (ref "DS1") (pin "9") (pinfunction "SDA_9") (pintype "input+no_connect"))
    )
    (net (code "92") (name "unconnected-(DS1-SQ-Pad12)") (class "Default")
      (node (ref "DS1") (pin "12") (pinfunction "SQ_12") (pintype "input+no_connect"))
    )
    (net (code "93") (name "unconnected-(H1-Pad2)") (class "Default")
      (node (ref "H1") (pin "2") (pinfunction "2_2") (pintype "unspecified+no_connect"))
    )
    (net (code "94") (name "unconnected-(H2-Pad2)") (class "Default")
      (node (ref "H2") (pin "2") (pinfunction "2_2") (pintype "unspecified+no_connect"))
    )
    (net (code "95") (name "unconnected-(HGG1-0-Pad10)") (class "Default")
      (node (ref "HGG1") (pin "10") (pinfunction "0_10") (pintype "input"))
    )
    (net (code "96") (name "unconnected-(HGG1-NC-Pad11)") (class "Default")
      (node (ref "HGG1") (pin "11") (pinfunction "NC_11") (pintype "input+no_connect"))
    )
    (net (code "97") (name "unconnected-(HGG1-NC-Pad13)") (class "Default")
      (node (ref "HGG1") (pin "13") (pinfunction "NC_13") (pintype "input+no_connect"))
    )
    (net (code "98") (name "unconnected-(HGG1-NC-Pad14)") (class "Default")
      (node (ref "HGG1") (pin "14") (pinfunction "NC_14") (pintype "input+no_connect"))
    )
    (net (code "99") (name "unconnected-(HGG1-Pad3)") (class "Default")
      (node (ref "HGG1") (pin "3") (pinfunction "3_3") (pintype "input"))
    )
    (net (code "100") (name "unconnected-(HGG1-Pad4)") (class "Default")
      (node (ref "HGG1") (pin "4") (pinfunction "4_4") (pintype "input"))
    )
    (net (code "101") (name "unconnected-(HGG1-Pad6)") (class "Default")
      (node (ref "HGG1") (pin "6") (pinfunction "6_6") (pintype "input"))
    )
    (net (code "102") (name "unconnected-(HGG1-Pad9)") (class "Default")
      (node (ref "HGG1") (pin "9") (pinfunction "9_9") (pintype "input"))
    )
    (net (code "103") (name "unconnected-(HGG2-NC-Pad11)") (class "Default")
      (node (ref "HGG2") (pin "11") (pinfunction "NC_11") (pintype "input+no_connect"))
    )
    (net (code "104") (name "unconnected-(HGG2-NC-Pad13)") (class "Default")
      (node (ref "HGG2") (pin "13") (pinfunction "NC_13") (pintype "input+no_connect"))
    )
    (net (code "105") (name "unconnected-(HGG2-NC-Pad14)") (class "Default")
      (node (ref "HGG2") (pin "14") (pinfunction "NC_14") (pintype "input+no_connect"))
    )
    (net (code "106") (name "unconnected-(HGG2-Pad3)") (class "Default")
      (node (ref "HGG2") (pin "3") (pinfunction "3_3") (pintype "input"))
    )
    (net (code "107") (name "unconnected-(HGG2-Pad4)") (class "Default")
      (node (ref "HGG2") (pin "4") (pinfunction "4_4") (pintype "input"))
    )
    (net (code "108") (name "unconnected-(HGG2-Pad6)") (class "Default")
      (node (ref "HGG2") (pin "6") (pinfunction "6_6") (pintype "input"))
    )
    (net (code "109") (name "unconnected-(HGG2-Pad9)") (class "Default")
      (node (ref "HGG2") (pin "9") (pinfunction "9_9") (pintype "input"))
    )
    (net (code "110") (name "unconnected-(HGG3-0-Pad10)") (class "Default")
      (node (ref "HGG3") (pin "10") (pinfunction "0_10") (pintype "input"))
    )
    (net (code "111") (name "unconnected-(HGG3-NC-Pad11)") (class "Default")
      (node (ref "HGG3") (pin "11") (pinfunction "NC_11") (pintype "input+no_connect"))
    )
    (net (code "112") (name "unconnected-(HGG3-NC-Pad13)") (class "Default")
      (node (ref "HGG3") (pin "13") (pinfunction "NC_13") (pintype "input+no_connect"))
    )
    (net (code "113") (name "unconnected-(HGG3-NC-Pad14)") (class "Default")
      (node (ref "HGG3") (pin "14") (pinfunction "NC_14") (pintype "input+no_connect"))
    )
    (net (code "114") (name "unconnected-(HGG3-Pad3)") (class "Default")
      (node (ref "HGG3") (pin "3") (pinfunction "3_3") (pintype "input"))
    )
    (net (code "115") (name "unconnected-(HGG3-Pad4)") (class "Default")
      (node (ref "HGG3") (pin "4") (pinfunction "4_4") (pintype "input"))
    )
    (net (code "116") (name "unconnected-(HGG3-Pad6)") (class "Default")
      (node (ref "HGG3") (pin "6") (pinfunction "6_6") (pintype "input"))
    )
    (net (code "117") (name "unconnected-(HGG3-Pad8)") (class "Default")
      (node (ref "HGG3") (pin "8") (pinfunction "8_8") (pintype "input"))
    )
    (net (code "118") (name "unconnected-(HGG3-Pad9)") (class "Default")
      (node (ref "HGG3") (pin "9") (pinfunction "9_9") (pintype "input"))
    )
    (net (code "119") (name "unconnected-(HGG4-0-Pad10)") (class "Default")
      (node (ref "HGG4") (pin "10") (pinfunction "0_10") (pintype "input"))
    )
    (net (code "120") (name "unconnected-(HGG4-NC-Pad11)") (class "Default")
      (node (ref "HGG4") (pin "11") (pinfunction "NC_11") (pintype "input+no_connect"))
    )
    (net (code "121") (name "unconnected-(HGG4-NC-Pad13)") (class "Default")
      (node (ref "HGG4") (pin "13") (pinfunction "NC_13") (pintype "input+no_connect"))
    )
    (net (code "122") (name "unconnected-(HGG4-NC-Pad14)") (class "Default")
      (node (ref "HGG4") (pin "14") (pinfunction "NC_14") (pintype "input+no_connect"))
    )
    (net (code "123") (name "unconnected-(HGG4-Pad3)") (class "Default")
      (node (ref "HGG4") (pin "3") (pinfunction "3_3") (pintype "input"))
    )
    (net (code "124") (name "unconnected-(HGG4-Pad4)") (class "Default")
      (node (ref "HGG4") (pin "4") (pinfunction "4_4") (pintype "input"))
    )
    (net (code "125") (name "unconnected-(HGG4-Pad6)") (class "Default")
      (node (ref "HGG4") (pin "6") (pinfunction "6_6") (pintype "input"))
    )
    (net (code "126") (name "unconnected-(HGG4-Pad8)") (class "Default")
      (node (ref "HGG4") (pin "8") (pinfunction "8_8") (pintype "input"))
    )
    (net (code "127") (name "unconnected-(HGG4-Pad9)") (class "Default")
      (node (ref "HGG4") (pin "9") (pinfunction "9_9") (pintype "input"))
    )
    (net (code "128") (name "unconnected-(HGG5-0-Pad10)") (class "Default")
      (node (ref "HGG5") (pin "10") (pinfunction "0_10") (pintype "input"))
    )
    (net (code "129") (name "unconnected-(HGG5-NC-Pad11)") (class "Default")
      (node (ref "HGG5") (pin "11") (pinfunction "NC_11") (pintype "input+no_connect"))
    )
    (net (code "130") (name "unconnected-(HGG5-NC-Pad13)") (class "Default")
      (node (ref "HGG5") (pin "13") (pinfunction "NC_13") (pintype "input+no_connect"))
    )
    (net (code "131") (name "unconnected-(HGG5-NC-Pad14)") (class "Default")
      (node (ref "HGG5") (pin "14") (pinfunction "NC_14") (pintype "input+no_connect"))
    )
    (net (code "132") (name "unconnected-(HGG5-Pad3)") (class "Default")
      (node (ref "HGG5") (pin "3") (pinfunction "3_3") (pintype "input"))
    )
    (net (code "133") (name "unconnected-(HGG5-Pad4)") (class "Default")
      (node (ref "HGG5") (pin "4") (pinfunction "4_4") (pintype "input"))
    )
    (net (code "134") (name "unconnected-(HGG5-Pad6)") (class "Default")
      (node (ref "HGG5") (pin "6") (pinfunction "6_6") (pintype "input"))
    )
    (net (code "135") (name "unconnected-(HGG5-Pad8)") (class "Default")
      (node (ref "HGG5") (pin "8") (pinfunction "8_8") (pintype "input"))
    )
    (net (code "136") (name "unconnected-(HGG5-Pad9)") (class "Default")
      (node (ref "HGG5") (pin "9") (pinfunction "9_9") (pintype "input"))
    )
    (net (code "137") (name "unconnected-(HGG6-0-Pad10)") (class "Default")
      (node (ref "HGG6") (pin "10") (pinfunction "0_10") (pintype "input"))
    )
    (net (code "138") (name "unconnected-(HGG6-NC-Pad11)") (class "Default")
      (node (ref "HGG6") (pin "11") (pinfunction "NC_11") (pintype "input+no_connect"))
    )
    (net (code "139") (name "unconnected-(HGG6-NC-Pad13)") (class "Default")
      (node (ref "HGG6") (pin "13") (pinfunction "NC_13") (pintype "input+no_connect"))
    )
    (net (code "140") (name "unconnected-(HGG6-NC-Pad14)") (class "Default")
      (node (ref "HGG6") (pin "14") (pinfunction "NC_14") (pintype "input+no_connect"))
    )
    (net (code "141") (name "unconnected-(HGG6-Pad3)") (class "Default")
      (node (ref "HGG6") (pin "3") (pinfunction "3_3") (pintype "input"))
    )
    (net (code "142") (name "unconnected-(HGG6-Pad4)") (class "Default")
      (node (ref "HGG6") (pin "4") (pinfunction "4_4") (pintype "input"))
    )
    (net (code "143") (name "unconnected-(HGG6-Pad6)") (class "Default")
      (node (ref "HGG6") (pin "6") (pinfunction "6_6") (pintype "input"))
    )
    (net (code "144") (name "unconnected-(HGG6-Pad8)") (class "Default")
      (node (ref "HGG6") (pin "8") (pinfunction "8_8") (pintype "input"))
    )
    (net (code "145") (name "unconnected-(HGG6-Pad9)") (class "Default")
      (node (ref "HGG6") (pin "9") (pinfunction "9_9") (pintype "input"))
    )
    (net (code "146") (name "unconnected-(KEY1-Pad1)") (class "Default")
      (node (ref "KEY1") (pin "1") (pinfunction "1_1") (pintype "input"))
    )
    (net (code "147") (name "unconnected-(KEY1-Pad3)") (class "Default")
      (node (ref "KEY1") (pin "3") (pinfunction "3_3") (pintype "input"))
    )
    (net (code "148") (name "unconnected-(KEY2-Pad1)") (class "Default")
      (node (ref "KEY2") (pin "1") (pinfunction "1_1") (pintype "input"))
    )
    (net (code "149") (name "unconnected-(KEY2-Pad3)") (class "Default")
      (node (ref "KEY2") (pin "3") (pinfunction "3_3") (pintype "input"))
    )
    (net (code "150") (name "unconnected-(U1-OUT--Pad4)") (class "Default")
      (node (ref "U1") (pin "4") (pinfunction "OUT-_4") (pintype "input"))
    )
    (net (code "151") (name "unconnected-(U3-GND-Pad4)") (class "Default")
      (node (ref "U3") (pin "4") (pinfunction "GND_4") (pintype "input"))
    )
    (net (code "152") (name "unconnected-(U4-3V3-Pad43)") (class "Default")
      (node (ref "U4") (pin "43") (pinfunction "3V3_43") (pintype "input"))
    )
    (net (code "153") (name "unconnected-(U4-5V-Pad42)") (class "Default")
      (node (ref "U4") (pin "42") (pinfunction "5V_42") (pintype "input"))
    )
    (net (code "154") (name "unconnected-(U4-A0-Pad8)") (class "Default")
      (node (ref "U4") (pin "8") (pinfunction "A0_8") (pintype "input"))
    )
    (net (code "155") (name "unconnected-(U4-A1-Pad35)") (class "Default")
      (node (ref "U4") (pin "35") (pinfunction "A1_35") (pintype "input"))
    )
    (net (code "156") (name "unconnected-(U4-A9-Pad57)") (class "Default")
      (node (ref "U4") (pin "57") (pinfunction "A9_57") (pintype "input+no_connect"))
    )
    (net (code "157") (name "unconnected-(U4-A10-Pad70)") (class "Default")
      (node (ref "U4") (pin "70") (pinfunction "A10_70") (pintype "input+no_connect"))
    )
    (net (code "158") (name "unconnected-(U4-A12-Pad55)") (class "Default")
      (node (ref "U4") (pin "55") (pinfunction "A12_55") (pintype "input"))
    )
    (net (code "159") (name "unconnected-(U4-A15-Pad72)") (class "Default")
      (node (ref "U4") (pin "72") (pinfunction "A15_72") (pintype "input"))
    )
    (net (code "160") (name "unconnected-(U4-B2-Pad14)") (class "Default")
      (node (ref "U4") (pin "14") (pinfunction "B2_14") (pintype "input+no_connect"))
    )
    (net (code "161") (name "unconnected-(U4-B3-Pad78)") (class "Default")
      (node (ref "U4") (pin "78") (pinfunction "B3_78") (pintype "input"))
    )
    (net (code "162") (name "unconnected-(U4-B4-Pad48)") (class "Default")
      (node (ref "U4") (pin "48") (pinfunction "B4_48") (pintype "input"))
    )
    (net (code "163") (name "unconnected-(U4-B5-Pad79)") (class "Default")
      (node (ref "U4") (pin "79") (pinfunction "B5_79") (pintype "input"))
    )
    (net (code "164") (name "unconnected-(U4-B8-Pad46)") (class "Default")
      (node (ref "U4") (pin "46") (pinfunction "B8_46") (pintype "input"))
    )
    (net (code "165") (name "unconnected-(U4-B9-Pad81)") (class "Default")
      (node (ref "U4") (pin "81") (pinfunction "B9_81") (pintype "input"))
    )
    (net (code "166") (name "unconnected-(U4-B11-Pad24)") (class "Default")
      (node (ref "U4") (pin "24") (pinfunction "B11_24") (pintype "input"))
    )
    (net (code "167") (name "unconnected-(U4-B13-Pad23)") (class "Default")
      (node (ref "U4") (pin "23") (pinfunction "B13_23") (pintype "input"))
    )
    (net (code "168") (name "unconnected-(U4-C2-Pad7)") (class "Default")
      (node (ref "U4") (pin "7") (pinfunction "C2_7") (pintype "input"))
    )
    (net (code "169") (name "unconnected-(U4-C3-Pad36)") (class "Default")
      (node (ref "U4") (pin "36") (pinfunction "C3_36") (pintype "input"))
    )
    (net (code "170") (name "unconnected-(U4-C5-Pad31)") (class "Default")
      (node (ref "U4") (pin "31") (pinfunction "C5_31") (pintype "input+no_connect"))
    )
    (net (code "171") (name "unconnected-(U4-C7-Pad68)") (class "Default")
      (node (ref "U4") (pin "68") (pinfunction "C7_68") (pintype "input"))
    )
    (net (code "172") (name "unconnected-(U4-C9-Pad69)") (class "Default")
      (node (ref "U4") (pin "69") (pinfunction "C9_69") (pintype "input"))
    )
    (net (code "173") (name "unconnected-(U4-C10-Pad54)") (class "Default")
      (node (ref "U4") (pin "54") (pinfunction "C10_54") (pintype "input"))
    )
    (net (code "174") (name "unconnected-(U4-C11-Pad73)") (class "Default")
      (node (ref "U4") (pin "73") (pinfunction "C11_73") (pintype "input"))
    )
    (net (code "175") (name "unconnected-(U4-C12-Pad53)") (class "Default")
      (node (ref "U4") (pin "53") (pinfunction "C12_53") (pintype "input"))
    )
    (net (code "176") (name "unconnected-(U4-D0-Pad74)") (class "Default")
      (node (ref "U4") (pin "74") (pinfunction "D0_74") (pintype "input"))
    )
    (net (code "177") (name "unconnected-(U4-D1-Pad52)") (class "Default")
      (node (ref "U4") (pin "52") (pinfunction "D1_52") (pintype "input"))
    )
    (net (code "178") (name "unconnected-(U4-D2-Pad75)") (class "Default")
      (node (ref "U4") (pin "75") (pinfunction "D2_75") (pintype "input"))
    )
    (net (code "179") (name "unconnected-(U4-D3-Pad51)") (class "Default")
      (node (ref "U4") (pin "51") (pinfunction "D3_51") (pintype "input"))
    )
    (net (code "180") (name "unconnected-(U4-D4-Pad76)") (class "Default")
      (node (ref "U4") (pin "76") (pinfunction "D4_76") (pintype "input"))
    )
    (net (code "181") (name "unconnected-(U4-D5-Pad50)") (class "Default")
      (node (ref "U4") (pin "50") (pinfunction "D5_50") (pintype "input"))
    )
    (net (code "182") (name "unconnected-(U4-D6-Pad77)") (class "Default")
      (node (ref "U4") (pin "77") (pinfunction "D6_77") (pintype "input"))
    )
    (net (code "183") (name "unconnected-(U4-D7-Pad49)") (class "Default")
      (node (ref "U4") (pin "49") (pinfunction "D7_49") (pintype "input"))
    )
    (net (code "184") (name "unconnected-(U4-D9-Pad64)") (class "Default")
      (node (ref "U4") (pin "64") (pinfunction "D9_64") (pintype "input"))
    )
    (net (code "185") (name "unconnected-(U4-D11-Pad65)") (class "Default")
      (node (ref "U4") (pin "65") (pinfunction "D11_65") (pintype "input"))
    )
    (net (code "186") (name "unconnected-(U4-D13-Pad66)") (class "Default")
      (node (ref "U4") (pin "66") (pinfunction "D13_66") (pintype "input"))
    )
    (net (code "187") (name "unconnected-(U4-D15-Pad67)") (class "Default")
      (node (ref "U4") (pin "67") (pinfunction "D15_67") (pintype "input"))
    )
    (net (code "188") (name "unconnected-(U4-E0-Pad45)") (class "Default")
      (node (ref "U4") (pin "45") (pinfunction "E0_45") (pintype "input"))
    )
    (net (code "189") (name "unconnected-(U4-E1-Pad82)") (class "Default")
      (node (ref "U4") (pin "82") (pinfunction "E1_82") (pintype "input"))
    )
    (net (code "190") (name "unconnected-(U4-E9-Pad28)") (class "Default")
      (node (ref "U4") (pin "28") (pinfunction "E9_28") (pintype "input"))
    )
    (net (code "191") (name "unconnected-(U4-E11-Pad27)") (class "Default")
      (node (ref "U4") (pin "27") (pinfunction "E11_27") (pintype "input"))
    )
    (net (code "192") (name "unconnected-(U4-E13-Pad26)") (class "Default")
      (node (ref "U4") (pin "26") (pinfunction "E13_26") (pintype "input"))
    )
    (net (code "193") (name "unconnected-(U4-E15-Pad25)") (class "Default")
      (node (ref "U4") (pin "25") (pinfunction "E15_25") (pintype "input"))
    )
    (net (code "194") (name "unconnected-(U4-GND-Pad41)") (class "Default")
      (node (ref "U4") (pin "41") (pinfunction "GND_41") (pintype "input"))
    )
    (net (code "195") (name "unconnected-(U4-GND-Pad44)") (class "Default")
      (node (ref "U4") (pin "44") (pinfunction "GND_44") (pintype "input"))
    )
    (net (code "196") (name "unconnected-(U4-GND-Pad83)") (class "Default")
      (node (ref "U4") (pin "83") (pinfunction "GND_83") (pintype "input"))
    )
    (net (code "197") (name "unconnected-(U5-IO0-Pad3)") (class "Default")
      (node (ref "U5") (pin "3") (pinfunction "IO0_3") (pintype "input"))
    )
    (net (code "198") (name "unconnected-(U5-IO2-Pad2)") (class "Default")
      (node (ref "U5") (pin "2") (pinfunction "IO2_2") (pintype "input"))
    )
    (net (code "199") (name "unconnected-(X1-+5-Pad5)") (class "Default")
      (node (ref "X1") (pin "5") (pinfunction "+5_5") (pintype "input"))
    )
    (net (code "200") (name "unconnected-(X1-1-Pad15)") (class "Default")
      (node (ref "X1") (pin "15") (pinfunction "1_15") (pintype "input"))
    )
    (net (code "201") (name "unconnected-(X1-2-Pad8)") (class "Default")
      (node (ref "X1") (pin "8") (pinfunction "2_8") (pintype "input"))
    )
    (net (code "202") (name "unconnected-(X1-3-Pad9)") (class "Default")
      (node (ref "X1") (pin "9") (pinfunction "3_9") (pintype "input"))
    )
    (net (code "203") (name "unconnected-(X1-4-Pad13)") (class "Default")
      (node (ref "X1") (pin "13") (pinfunction "4_13") (pintype "input"))
    )
    (net (code "204") (name "unconnected-(X1-5-Pad14)") (class "Default")
      (node (ref "X1") (pin "14") (pinfunction "5_14") (pintype "input"))
    )
    (net (code "205") (name "unconnected-(X1-6-Pad11)") (class "Default")
      (node (ref "X1") (pin "11") (pinfunction "6_11") (pintype "input"))
    )
    (net (code "206") (name "unconnected-(X1-A-Pad3)") (class "Default")
      (node (ref "X1") (pin "3") (pinfunction "A_3") (pintype "input"))
    )
    (net (code "207") (name "unconnected-(X1-B-Pad6)") (class "Default")
      (node (ref "X1") (pin "6") (pinfunction "B_6") (pintype "input"))
    )
    (net (code "208") (name "unconnected-(X1-GND-Pad12)") (class "Default")
      (node (ref "X1") (pin "12") (pinfunction "GND_12") (pintype "input"))
    )
    (net (code "209") (name "unconnected-(X2-+5-Pad5)") (class "Default")
      (node (ref "X2") (pin "5") (pinfunction "+5_5") (pintype "input"))
    )
    (net (code "210") (name "unconnected-(X2-1-Pad15)") (class "Default")
      (node (ref "X2") (pin "15") (pinfunction "1_15") (pintype "input"))
    )
    (net (code "211") (name "unconnected-(X2-2-Pad8)") (class "Default")
      (node (ref "X2") (pin "8") (pinfunction "2_8") (pintype "input"))
    )
    (net (code "212") (name "unconnected-(X2-3-Pad9)") (class "Default")
      (node (ref "X2") (pin "9") (pinfunction "3_9") (pintype "input"))
    )
    (net (code "213") (name "unconnected-(X2-4-Pad13)") (class "Default")
      (node (ref "X2") (pin "13") (pinfunction "4_13") (pintype "input"))
    )
    (net (code "214") (name "unconnected-(X2-5-Pad14)") (class "Default")
      (node (ref "X2") (pin "14") (pinfunction "5_14") (pintype "input"))
    )
    (net (code "215") (name "unconnected-(X2-6-Pad11)") (class "Default")
      (node (ref "X2") (pin "11") (pinfunction "6_11") (pintype "input"))
    )
    (net (code "216") (name "unconnected-(X2-A-Pad3)") (class "Default")
      (node (ref "X2") (pin "3") (pinfunction "A_3") (pintype "input"))
    )
    (net (code "217") (name "unconnected-(X2-B-Pad6)") (class "Default")
      (node (ref "X2") (pin "6") (pinfunction "B_6") (pintype "input"))
    )
    (net (code "218") (name "unconnected-(X2-GND-Pad12)") (class "Default")
      (node (ref "X2") (pin "12") (pinfunction "GND_12") (pintype "input"))
    )
    (net (code "219") (name "unconnected-(X3-+5-Pad5)") (class "Default")
      (node (ref "X3") (pin "5") (pinfunction "+5_5") (pintype "input"))
    )
    (net (code "220") (name "unconnected-(X3-1-Pad15)") (class "Default")
      (node (ref "X3") (pin "15") (pinfunction "1_15") (pintype "input"))
    )
    (net (code "221") (name "unconnected-(X3-2-Pad8)") (class "Default")
      (node (ref "X3") (pin "8") (pinfunction "2_8") (pintype "input"))
    )
    (net (code "222") (name "unconnected-(X3-3-Pad9)") (class "Default")
      (node (ref "X3") (pin "9") (pinfunction "3_9") (pintype "input"))
    )
    (net (code "223") (name "unconnected-(X3-4-Pad13)") (class "Default")
      (node (ref "X3") (pin "13") (pinfunction "4_13") (pintype "input"))
    )
    (net (code "224") (name "unconnected-(X3-5-Pad14)") (class "Default")
      (node (ref "X3") (pin "14") (pinfunction "5_14") (pintype "input"))
    )
    (net (code "225") (name "unconnected-(X3-6-Pad11)") (class "Default")
      (node (ref "X3") (pin "11") (pinfunction "6_11") (pintype "input"))
    )
    (net (code "226") (name "unconnected-(X3-A-Pad3)") (class "Default")
      (node (ref "X3") (pin "3") (pinfunction "A_3") (pintype "input"))
    )
    (net (code "227") (name "unconnected-(X3-B-Pad6)") (class "Default")
      (node (ref "X3") (pin "6") (pinfunction "B_6") (pintype "input"))
    )
    (net (code "228") (name "unconnected-(X3-GND-Pad12)") (class "Default")
      (node (ref "X3") (pin "12") (pinfunction "GND_12") (pintype "input"))
    )
    (net (code "229") (name "unconnected-(X4-+5-Pad5)") (class "Default")
      (node (ref "X4") (pin "5") (pinfunction "+5_5") (pintype "input"))
    )
    (net (code "230") (name "unconnected-(X4-1-Pad15)") (class "Default")
      (node (ref "X4") (pin "15") (pinfunction "1_15") (pintype "input"))
    )
    (net (code "231") (name "unconnected-(X4-2-Pad8)") (class "Default")
      (node (ref "X4") (pin "8") (pinfunction "2_8") (pintype "input"))
    )
    (net (code "232") (name "unconnected-(X4-3-Pad9)") (class "Default")
      (node (ref "X4") (pin "9") (pinfunction "3_9") (pintype "input"))
    )
    (net (code "233") (name "unconnected-(X4-4-Pad13)") (class "Default")
      (node (ref "X4") (pin "13") (pinfunction "4_13") (pintype "input"))
    )
    (net (code "234") (name "unconnected-(X4-5-Pad14)") (class "Default")
      (node (ref "X4") (pin "14") (pinfunction "5_14") (pintype "input"))
    )
    (net (code "235") (name "unconnected-(X4-6-Pad11)") (class "Default")
      (node (ref "X4") (pin "11") (pinfunction "6_11") (pintype "input"))
    )
    (net (code "236") (name "unconnected-(X4-A-Pad3)") (class "Default")
      (node (ref "X4") (pin "3") (pinfunction "A_3") (pintype "input"))
    )
    (net (code "237") (name "unconnected-(X4-B-Pad6)") (class "Default")
      (node (ref "X4") (pin "6") (pinfunction "B_6") (pintype "input"))
    )
    (net (code "238") (name "unconnected-(X4-GND-Pad12)") (class "Default")
      (node (ref "X4") (pin "12") (pinfunction "GND_12") (pintype "input"))
    )
    (net (code "239") (name "unconnected-(X5-+5-Pad5)") (class "Default")
      (node (ref "X5") (pin "5") (pinfunction "+5_5") (pintype "input"))
    )
    (net (code "240") (name "unconnected-(X5-1-Pad15)") (class "Default")
      (node (ref "X5") (pin "15") (pinfunction "1_15") (pintype "input"))
    )
    (net (code "241") (name "unconnected-(X5-2-Pad8)") (class "Default")
      (node (ref "X5") (pin "8") (pinfunction "2_8") (pintype "input"))
    )
    (net (code "242") (name "unconnected-(X5-3-Pad9)") (class "Default")
      (node (ref "X5") (pin "9") (pinfunction "3_9") (pintype "input"))
    )
    (net (code "243") (name "unconnected-(X5-4-Pad13)") (class "Default")
      (node (ref "X5") (pin "13") (pinfunction "4_13") (pintype "input"))
    )
    (net (code "244") (name "unconnected-(X5-5-Pad14)") (class "Default")
      (node (ref "X5") (pin "14") (pinfunction "5_14") (pintype "input"))
    )
    (net (code "245") (name "unconnected-(X5-6-Pad11)") (class "Default")
      (node (ref "X5") (pin "11") (pinfunction "6_11") (pintype "input"))
    )
    (net (code "246") (name "unconnected-(X5-A-Pad3)") (class "Default")
      (node (ref "X5") (pin "3") (pinfunction "A_3") (pintype "input"))
    )
    (net (code "247") (name "unconnected-(X5-B-Pad6)") (class "Default")
      (node (ref "X5") (pin "6") (pinfunction "B_6") (pintype "input"))
    )
    (net (code "248") (name "unconnected-(X6-1-Pad15)") (class "Default")
      (node (ref "X6") (pin "15") (pinfunction "1_15") (pintype "input"))
    )
    (net (code "249") (name "unconnected-(X6-2-Pad8)") (class "Default")
      (node (ref "X6") (pin "8") (pinfunction "2_8") (pintype "input"))
    )
    (net (code "250") (name "unconnected-(X6-3-Pad9)") (class "Default")
      (node (ref "X6") (pin "9") (pinfunction "3_9") (pintype "input"))
    )
    (net (code "251") (name "unconnected-(X6-4-Pad13)") (class "Default")
      (node (ref "X6") (pin "13") (pinfunction "4_13") (pintype "input"))
    )
    (net (code "252") (name "unconnected-(X6-5-Pad14)") (class "Default")
      (node (ref "X6") (pin "14") (pinfunction "5_14") (pintype "input"))
    )
    (net (code "253") (name "unconnected-(X6-6-Pad11)") (class "Default")
      (node (ref "X6") (pin "11") (pinfunction "6_11") (pintype "input"))
    )
    (net (code "254") (name "unconnected-(X6-A-Pad3)") (class "Default")
      (node (ref "X6") (pin "3") (pinfunction "A_3") (pintype "input"))
    )
    (net (code "255") (name "unconnected-(X6-B-Pad6)") (class "Default")
      (node (ref "X6") (pin "6") (pinfunction "B_6") (pintype "input"))
    )
  )
)
